# B2B_Connectors.net
KiCad netlist of a schematic drawn in Altium Designer
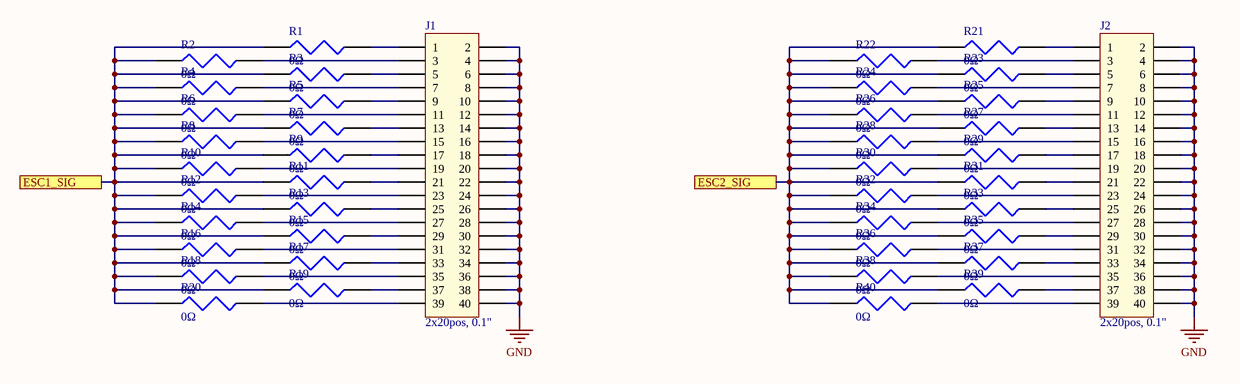
[diagram p0: B2B_Connectors.SchDoc]

(export (version "E")
  (design (tool "Eeschema 10.0.6"))
  (components
    (comp (ref "J1")
      (value "2x20pos, 0.1\"")
      (footprint "1979")
      (description "Adafruit STACKING HEADER RASPBERRY PI")
      (fields (field (name "MANUFACTURER") "Adafruit") (field (name "PART NUMBER") "1979"))
      (libsource (lib "MinesROV") (part "1979"))
    )
    (comp (ref "J2")
      (value "2x20pos, 0.1\"")
      (footprint "1979")
      (description "Adafruit STACKING HEADER RASPBERRY PI")
      (fields (field (name "MANUFACTURER") "Adafruit") (field (name "PART NUMBER") "1979"))
      (libsource (lib "MinesROV") (part "1979"))
    )
    (comp (ref "R1")
      (value "0Ω")
      (footprint "RMCF1206")
      (description "Stackpole RES 0 OHM 1/4W 1206")
      (fields
        (field (name "PART NUMBER") "RMCF1206ZT0R00")
        (field (name "MANUFACTURER") "Stackpole Electronics Inc")
      )
      (libsource (lib "MinesROV") (part "RMCF1206ZT0R00"))
    )
    (comp (ref "R2")
      (value "0Ω")
      (footprint "RMCF1206")
      (description "Stackpole RES 0 OHM 1/4W 1206")
      (fields
        (field (name "PART NUMBER") "RMCF1206ZT0R00")
        (field (name "MANUFACTURER") "Stackpole Electronics Inc")
      )
      (libsource (lib "MinesROV") (part "RMCF1206ZT0R00"))
    )
    (comp (ref "R3")
      (value "0Ω")
      (footprint "RMCF1206")
      (description "Stackpole RES 0 OHM 1/4W 1206")
      (fields
        (field (name "PART NUMBER") "RMCF1206ZT0R00")
        (field (name "MANUFACTURER") "Stackpole Electronics Inc")
      )
      (libsource (lib "MinesROV") (part "RMCF1206ZT0R00"))
    )
    (comp (ref "R4")
      (value "0Ω")
      (footprint "RMCF1206")
      (description "Stackpole RES 0 OHM 1/4W 1206")
      (fields
        (field (name "PART NUMBER") "RMCF1206ZT0R00")
        (field (name "MANUFACTURER") "Stackpole Electronics Inc")
      )
      (libsource (lib "MinesROV") (part "RMCF1206ZT0R00"))
    )
    (comp (ref "R5")
      (value "0Ω")
      (footprint "RMCF1206")
      (description "Stackpole RES 0 OHM 1/4W 1206")
      (fields
        (field (name "PART NUMBER") "RMCF1206ZT0R00")
        (field (name "MANUFACTURER") "Stackpole Electronics Inc")
      )
      (libsource (lib "MinesROV") (part "RMCF1206ZT0R00"))
    )
    (comp (ref "R6")
      (value "0Ω")
      (footprint "RMCF1206")
      (description "Stackpole RES 0 OHM 1/4W 1206")
      (fields
        (field (name "PART NUMBER") "RMCF1206ZT0R00")
        (field (name "MANUFACTURER") "Stackpole Electronics Inc")
      )
      (libsource (lib "MinesROV") (part "RMCF1206ZT0R00"))
    )
    (comp (ref "R7")
      (value "0Ω")
      (footprint "RMCF1206")
      (description "Stackpole RES 0 OHM 1/4W 1206")
      (fields
        (field (name "PART NUMBER") "RMCF1206ZT0R00")
        (field (name "MANUFACTURER") "Stackpole Electronics Inc")
      )
      (libsource (lib "MinesROV") (part "RMCF1206ZT0R00"))
    )
    (comp (ref "R8")
      (value "0Ω")
      (footprint "RMCF1206")
      (description "Stackpole RES 0 OHM 1/4W 1206")
      (fields
        (field (name "PART NUMBER") "RMCF1206ZT0R00")
        (field (name "MANUFACTURER") "Stackpole Electronics Inc")
      )
      (libsource (lib "MinesROV") (part "RMCF1206ZT0R00"))
    )
    (comp (ref "R9")
      (value "0Ω")
      (footprint "RMCF1206")
      (description "Stackpole RES 0 OHM 1/4W 1206")
      (fields
        (field (name "PART NUMBER") "RMCF1206ZT0R00")
        (field (name "MANUFACTURER") "Stackpole Electronics Inc")
      )
      (libsource (lib "MinesROV") (part "RMCF1206ZT0R00"))
    )
    (comp (ref "R10")
      (value "0Ω")
      (footprint "RMCF1206")
      (description "Stackpole RES 0 OHM 1/4W 1206")
      (fields
        (field (name "PART NUMBER") "RMCF1206ZT0R00")
        (field (name "MANUFACTURER") "Stackpole Electronics Inc")
      )
      (libsource (lib "MinesROV") (part "RMCF1206ZT0R00"))
    )
    (comp (ref "R11")
      (value "0Ω")
      (footprint "RMCF1206")
      (description "Stackpole RES 0 OHM 1/4W 1206")
      (fields
        (field (name "PART NUMBER") "RMCF1206ZT0R00")
        (field (name "MANUFACTURER") "Stackpole Electronics Inc")
      )
      (libsource (lib "MinesROV") (part "RMCF1206ZT0R00"))
    )
    (comp (ref "R12")
      (value "0Ω")
      (footprint "RMCF1206")
      (description "Stackpole RES 0 OHM 1/4W 1206")
      (fields
        (field (name "PART NUMBER") "RMCF1206ZT0R00")
        (field (name "MANUFACTURER") "Stackpole Electronics Inc")
      )
      (libsource (lib "MinesROV") (part "RMCF1206ZT0R00"))
    )
    (comp (ref "R13")
      (value "0Ω")
      (footprint "RMCF1206")
      (description "Stackpole RES 0 OHM 1/4W 1206")
      (fields
        (field (name "PART NUMBER") "RMCF1206ZT0R00")
        (field (name "MANUFACTURER") "Stackpole Electronics Inc")
      )
      (libsource (lib "MinesROV") (part "RMCF1206ZT0R00"))
    )
    (comp (ref "R14")
      (value "0Ω")
      (footprint "RMCF1206")
      (description "Stackpole RES 0 OHM 1/4W 1206")
      (fields
        (field (name "PART NUMBER") "RMCF1206ZT0R00")
        (field (name "MANUFACTURER") "Stackpole Electronics Inc")
      )
      (libsource (lib "MinesROV") (part "RMCF1206ZT0R00"))
    )
    (comp (ref "R15")
      (value "0Ω")
      (footprint "RMCF1206")
      (description "Stackpole RES 0 OHM 1/4W 1206")
      (fields
        (field (name "PART NUMBER") "RMCF1206ZT0R00")
        (field (name "MANUFACTURER") "Stackpole Electronics Inc")
      )
      (libsource (lib "MinesROV") (part "RMCF1206ZT0R00"))
    )
    (comp (ref "R16")
      (value "0Ω")
      (footprint "RMCF1206")
      (description "Stackpole RES 0 OHM 1/4W 1206")
      (fields
        (field (name "PART NUMBER") "RMCF1206ZT0R00")
        (field (name "MANUFACTURER") "Stackpole Electronics Inc")
      )
      (libsource (lib "MinesROV") (part "RMCF1206ZT0R00"))
    )
    (comp (ref "R17")
      (value "0Ω")
      (footprint "RMCF1206")
      (description "Stackpole RES 0 OHM 1/4W 1206")
      (fields
        (field (name "PART NUMBER") "RMCF1206ZT0R00")
        (field (name "MANUFACTURER") "Stackpole Electronics Inc")
      )
      (libsource (lib "MinesROV") (part "RMCF1206ZT0R00"))
    )
    (comp (ref "R18")
      (value "0Ω")
      (footprint "RMCF1206")
      (description "Stackpole RES 0 OHM 1/4W 1206")
      (fields
        (field (name "PART NUMBER") "RMCF1206ZT0R00")
        (field (name "MANUFACTURER") "Stackpole Electronics Inc")
      )
      (libsource (lib "MinesROV") (part "RMCF1206ZT0R00"))
    )
    (comp (ref "R19")
      (value "0Ω")
      (footprint "RMCF1206")
      (description "Stackpole RES 0 OHM 1/4W 1206")
      (fields
        (field (name "PART NUMBER") "RMCF1206ZT0R00")
        (field (name "MANUFACTURER") "Stackpole Electronics Inc")
      )
      (libsource (lib "MinesROV") (part "RMCF1206ZT0R00"))
    )
    (comp (ref "R20")
      (value "0Ω")
      (footprint "RMCF1206")
      (description "Stackpole RES 0 OHM 1/4W 1206")
      (fields
        (field (name "PART NUMBER") "RMCF1206ZT0R00")
        (field (name "MANUFACTURER") "Stackpole Electronics Inc")
      )
      (libsource (lib "MinesROV") (part "RMCF1206ZT0R00"))
    )
    (comp (ref "R21")
      (value "0Ω")
      (footprint "RMCF1206")
      (description "Stackpole RES 0 OHM 1/4W 1206")
      (fields
        (field (name "PART NUMBER") "RMCF1206ZT0R00")
        (field (name "MANUFACTURER") "Stackpole Electronics Inc")
      )
      (libsource (lib "MinesROV") (part "RMCF1206ZT0R00"))
    )
    (comp (ref "R22")
      (value "0Ω")
      (footprint "RMCF1206")
      (description "Stackpole RES 0 OHM 1/4W 1206")
      (fields
        (field (name "PART NUMBER") "RMCF1206ZT0R00")
        (field (name "MANUFACTURER") "Stackpole Electronics Inc")
      )
      (libsource (lib "MinesROV") (part "RMCF1206ZT0R00"))
    )
    (comp (ref "R23")
      (value "0Ω")
      (footprint "RMCF1206")
      (description "Stackpole RES 0 OHM 1/4W 1206")
      (fields
        (field (name "PART NUMBER") "RMCF1206ZT0R00")
        (field (name "MANUFACTURER") "Stackpole Electronics Inc")
      )
      (libsource (lib "MinesROV") (part "RMCF1206ZT0R00"))
    )
    (comp (ref "R24")
      (value "0Ω")
      (footprint "RMCF1206")
      (description "Stackpole RES 0 OHM 1/4W 1206")
      (fields
        (field (name "PART NUMBER") "RMCF1206ZT0R00")
        (field (name "MANUFACTURER") "Stackpole Electronics Inc")
      )
      (libsource (lib "MinesROV") (part "RMCF1206ZT0R00"))
    )
    (comp (ref "R25")
      (value "0Ω")
      (footprint "RMCF1206")
      (description "Stackpole RES 0 OHM 1/4W 1206")
      (fields
        (field (name "PART NUMBER") "RMCF1206ZT0R00")
        (field (name "MANUFACTURER") "Stackpole Electronics Inc")
      )
      (libsource (lib "MinesROV") (part "RMCF1206ZT0R00"))
    )
    (comp (ref "R26")
      (value "0Ω")
      (footprint "RMCF1206")
      (description "Stackpole RES 0 OHM 1/4W 1206")
      (fields
        (field (name "PART NUMBER") "RMCF1206ZT0R00")
        (field (name "MANUFACTURER") "Stackpole Electronics Inc")
      )
      (libsource (lib "MinesROV") (part "RMCF1206ZT0R00"))
    )
    (comp (ref "R27")
      (value "0Ω")
      (footprint "RMCF1206")
      (description "Stackpole RES 0 OHM 1/4W 1206")
      (fields
        (field (name "PART NUMBER") "RMCF1206ZT0R00")
        (field (name "MANUFACTURER") "Stackpole Electronics Inc")
      )
      (libsource (lib "MinesROV") (part "RMCF1206ZT0R00"))
    )
    (comp (ref "R28")
      (value "0Ω")
      (footprint "RMCF1206")
      (description "Stackpole RES 0 OHM 1/4W 1206")
      (fields
        (field (name "PART NUMBER") "RMCF1206ZT0R00")
        (field (name "MANUFACTURER") "Stackpole Electronics Inc")
      )
      (libsource (lib "MinesROV") (part "RMCF1206ZT0R00"))
    )
    (comp (ref "R29")
      (value "0Ω")
      (footprint "RMCF1206")
      (description "Stackpole RES 0 OHM 1/4W 1206")
      (fields
        (field (name "PART NUMBER") "RMCF1206ZT0R00")
        (field (name "MANUFACTURER") "Stackpole Electronics Inc")
      )
      (libsource (lib "MinesROV") (part "RMCF1206ZT0R00"))
    )
    (comp (ref "R30")
      (value "0Ω")
      (footprint "RMCF1206")
      (description "Stackpole RES 0 OHM 1/4W 1206")
      (fields
        (field (name "PART NUMBER") "RMCF1206ZT0R00")
        (field (name "MANUFACTURER") "Stackpole Electronics Inc")
      )
      (libsource (lib "MinesROV") (part "RMCF1206ZT0R00"))
    )
    (comp (ref "R31")
      (value "0Ω")
      (footprint "RMCF1206")
      (description "Stackpole RES 0 OHM 1/4W 1206")
      (fields
        (field (name "PART NUMBER") "RMCF1206ZT0R00")
        (field (name "MANUFACTURER") "Stackpole Electronics Inc")
      )
      (libsource (lib "MinesROV") (part "RMCF1206ZT0R00"))
    )
    (comp (ref "R32")
      (value "0Ω")
      (footprint "RMCF1206")
      (description "Stackpole RES 0 OHM 1/4W 1206")
      (fields
        (field (name "PART NUMBER") "RMCF1206ZT0R00")
        (field (name "MANUFACTURER") "Stackpole Electronics Inc")
      )
      (libsource (lib "MinesROV") (part "RMCF1206ZT0R00"))
    )
    (comp (ref "R33")
      (value "0Ω")
      (footprint "RMCF1206")
      (description "Stackpole RES 0 OHM 1/4W 1206")
      (fields
        (field (name "PART NUMBER") "RMCF1206ZT0R00")
        (field (name "MANUFACTURER") "Stackpole Electronics Inc")
      )
      (libsource (lib "MinesROV") (part "RMCF1206ZT0R00"))
    )
    (comp (ref "R34")
      (value "0Ω")
      (footprint "RMCF1206")
      (description "Stackpole RES 0 OHM 1/4W 1206")
      (fields
        (field (name "PART NUMBER") "RMCF1206ZT0R00")
        (field (name "MANUFACTURER") "Stackpole Electronics Inc")
      )
      (libsource (lib "MinesROV") (part "RMCF1206ZT0R00"))
    )
    (comp (ref "R35")
      (value "0Ω")
      (footprint "RMCF1206")
      (description "Stackpole RES 0 OHM 1/4W 1206")
      (fields
        (field (name "PART NUMBER") "RMCF1206ZT0R00")
        (field (name "MANUFACTURER") "Stackpole Electronics Inc")
      )
      (libsource (lib "MinesROV") (part "RMCF1206ZT0R00"))
    )
    (comp (ref "R36")
      (value "0Ω")
      (footprint "RMCF1206")
      (description "Stackpole RES 0 OHM 1/4W 1206")
      (fields
        (field (name "PART NUMBER") "RMCF1206ZT0R00")
        (field (name "MANUFACTURER") "Stackpole Electronics Inc")
      )
      (libsource (lib "MinesROV") (part "RMCF1206ZT0R00"))
    )
    (comp (ref "R37")
      (value "0Ω")
      (footprint "RMCF1206")
      (description "Stackpole RES 0 OHM 1/4W 1206")
      (fields
        (field (name "PART NUMBER") "RMCF1206ZT0R00")
        (field (name "MANUFACTURER") "Stackpole Electronics Inc")
      )
      (libsource (lib "MinesROV") (part "RMCF1206ZT0R00"))
    )
    (comp (ref "R38")
      (value "0Ω")
      (footprint "RMCF1206")
      (description "Stackpole RES 0 OHM 1/4W 1206")
      (fields
        (field (name "PART NUMBER") "RMCF1206ZT0R00")
        (field (name "MANUFACTURER") "Stackpole Electronics Inc")
      )
      (libsource (lib "MinesROV") (part "RMCF1206ZT0R00"))
    )
    (comp (ref "R39")
      (value "0Ω")
      (footprint "RMCF1206")
      (description "Stackpole RES 0 OHM 1/4W 1206")
      (fields
        (field (name "PART NUMBER") "RMCF1206ZT0R00")
        (field (name "MANUFACTURER") "Stackpole Electronics Inc")
      )
      (libsource (lib "MinesROV") (part "RMCF1206ZT0R00"))
    )
    (comp (ref "R40")
      (value "0Ω")
      (footprint "RMCF1206")
      (description "Stackpole RES 0 OHM 1/4W 1206")
      (fields
        (field (name "PART NUMBER") "RMCF1206ZT0R00")
        (field (name "MANUFACTURER") "Stackpole Electronics Inc")
      )
      (libsource (lib "MinesROV") (part "RMCF1206ZT0R00"))
    )
  )
  (nets
    (net (code "1") (name "/ESC1_SIG") (class "Default")
      (node (ref "R1") (pin "1") (pinfunction "1_1") (pintype "passive"))
      (node (ref "R10") (pin "1") (pinfunction "1_1") (pintype "passive"))
      (node (ref "R11") (pin "1") (pinfunction "1_1") (pintype "passive"))
      (node (ref "R12") (pin "1") (pinfunction "1_1") (pintype "passive"))
      (node (ref "R13") (pin "1") (pinfunction "1_1") (pintype "passive"))
      (node (ref "R14") (pin "1") (pinfunction "1_1") (pintype "passive"))
      (node (ref "R15") (pin "1") (pinfunction "1_1") (pintype "passive"))
      (node (ref "R16") (pin "1") (pinfunction "1_1") (pintype "passive"))
      (node (ref "R17") (pin "1") (pinfunction "1_1") (pintype "passive"))
      (node (ref "R18") (pin "1") (pinfunction "1_1") (pintype "passive"))
      (node (ref "R19") (pin "1") (pinfunction "1_1") (pintype "passive"))
      (node (ref "R2") (pin "1") (pinfunction "1_1") (pintype "passive"))
      (node (ref "R20") (pin "1") (pinfunction "1_1") (pintype "passive"))
      (node (ref "R3") (pin "1") (pinfunction "1_1") (pintype "passive"))
      (node (ref "R4") (pin "1") (pinfunction "1_1") (pintype "passive"))
      (node (ref "R5") (pin "1") (pinfunction "1_1") (pintype "passive"))
      (node (ref "R6") (pin "1") (pinfunction "1_1") (pintype "passive"))
      (node (ref "R7") (pin "1") (pinfunction "1_1") (pintype "passive"))
      (node (ref "R8") (pin "1") (pinfunction "1_1") (pintype "passive"))
      (node (ref "R9") (pin "1") (pinfunction "1_1") (pintype "passive"))
    )
    (net (code "2") (name "/ESC2_SIG") (class "Default")
      (node (ref "R21") (pin "1") (pinfunction "1_1") (pintype "passive"))
      (node (ref "R22") (pin "1") (pinfunction "1_1") (pintype "passive"))
      (node (ref "R23") (pin "1") (pinfunction "1_1") (pintype "passive"))
      (node (ref "R24") (pin "1") (pinfunction "1_1") (pintype "passive"))
      (node (ref "R25") (pin "1") (pinfunction "1_1") (pintype "passive"))
      (node (ref "R26") (pin "1") (pinfunction "1_1") (pintype "passive"))
      (node (ref "R27") (pin "1") (pinfunction "1_1") (pintype "passive"))
      (node (ref "R28") (pin "1") (pinfunction "1_1") (pintype "passive"))
      (node (ref "R29") (pin "1") (pinfunction "1_1") (pintype "passive"))
      (node (ref "R30") (pin "1") (pinfunction "1_1") (pintype "passive"))
      (node (ref "R31") (pin "1") (pinfunction "1_1") (pintype "passive"))
      (node (ref "R32") (pin "1") (pinfunction "1_1") (pintype "passive"))
      (node (ref "R33") (pin "1") (pinfunction "1_1") (pintype "passive"))
      (node (ref "R34") (pin "1") (pinfunction "1_1") (pintype "passive"))
      (node (ref "R35") (pin "1") (pinfunction "1_1") (pintype "passive"))
      (node (ref "R36") (pin "1") (pinfunction "1_1") (pintype "passive"))
      (node (ref "R37") (pin "1") (pinfunction "1_1") (pintype "passive"))
      (node (ref "R38") (pin "1") (pinfunction "1_1") (pintype "passive"))
      (node (ref "R39") (pin "1") (pinfunction "1_1") (pintype "passive"))
      (node (ref "R40") (pin "1") (pinfunction "1_1") (pintype "passive"))
    )
    (net (code "3") (name "GND") (class "Default")
      (node (ref "J1") (pin "10") (pinfunction "10_10") (pintype "passive"))
      (node (ref "J1") (pin "12") (pinfunction "12_12") (pintype "passive"))
      (node (ref "J1") (pin "14") (pinfunction "14_14") (pintype "passive"))
      (node (ref "J1") (pin "16") (pinfunction "16_16") (pintype "passive"))
      (node (ref "J1") (pin "18") (pinfunction "18_18") (pintype "passive"))
      (node (ref "J1") (pin "2") (pinfunction "2_2") (pintype "passive"))
      (node (ref "J1") (pin "20") (pinfunction "20_20") (pintype "passive"))
      (node (ref "J1") (pin "22") (pinfunction "22_22") (pintype "passive"))
      (node (ref "J1") (pin "24") (pinfunction "24_24") (pintype "passive"))
      (node (ref "J1") (pin "26") (pinfunction "26_26") (pintype "passive"))
      (node (ref "J1") (pin "28") (pinfunction "28_28") (pintype "passive"))
      (node (ref "J1") (pin "30") (pinfunction "30_30") (pintype "passive"))
      (node (ref "J1") (pin "32") (pinfunction "32_32") (pintype "passive"))
      (node (ref "J1") (pin "34") (pinfunction "34_34") (pintype "passive"))
      (node (ref "J1") (pin "36") (pinfunction "36_36") (pintype "passive"))
      (node (ref "J1") (pin "38") (pinfunction "38_38") (pintype "passive"))
      (node (ref "J1") (pin "4") (pinfunction "4_4") (pintype "passive"))
      (node (ref "J1") (pin "40") (pinfunction "40_40") (pintype "passive"))
      (node (ref "J1") (pin "6") (pinfunction "6_6") (pintype "passive"))
      (node (ref "J1") (pin "8") (pinfunction "8_8") (pintype "passive"))
      (node (ref "J2") (pin "10") (pinfunction "10_10") (pintype "passive"))
      (node (ref "J2") (pin "12") (pinfunction "12_12") (pintype "passive"))
      (node (ref "J2") (pin "14") (pinfunction "14_14") (pintype "passive"))
      (node (ref "J2") (pin "16") (pinfunction "16_16") (pintype "passive"))
      (node (ref "J2") (pin "18") (pinfunction "18_18") (pintype "passive"))
      (node (ref "J2") (pin "2") (pinfunction "2_2") (pintype "passive"))
      (node (ref "J2") (pin "20") (pinfunction "20_20") (pintype "passive"))
      (node (ref "J2") (pin "22") (pinfunction "22_22") (pintype "passive"))
      (node (ref "J2") (pin "24") (pinfunction "24_24") (pintype "passive"))
      (node (ref "J2") (pin "26") (pinfunction "26_26") (pintype "passive"))
      (node (ref "J2") (pin "28") (pinfunction "28_28") (pintype "passive"))
      (node (ref "J2") (pin "30") (pinfunction "30_30") (pintype "passive"))
      (node (ref "J2") (pin "32") (pinfunction "32_32") (pintype "passive"))
      (node (ref "J2") (pin "34") (pinfunction "34_34") (pintype "passive"))
      (node (ref "J2") (pin "36") (pinfunction "36_36") (pintype "passive"))
      (node (ref "J2") (pin "38") (pinfunction "38_38") (pintype "passive"))
      (node (ref "J2") (pin "4") (pinfunction "4_4") (pintype "passive"))
      (node (ref "J2") (pin "40") (pinfunction "40_40") (pintype "passive"))
      (node (ref "J2") (pin "6") (pinfunction "6_6") (pintype "passive"))
      (node (ref "J2") (pin "8") (pinfunction "8_8") (pintype "passive"))
    )
    (net (code "4") (name "Net-(J1-Pad1)") (class "Default")
      (node (ref "J1") (pin "1") (pinfunction "1_1") (pintype "passive"))
      (node (ref "R1") (pin "2") (pinfunction "2_2") (pintype "passive"))
    )
    (net (code "5") (name "Net-(J1-Pad3)") (class "Default")
      (node (ref "J1") (pin "3") (pinfunction "3_3") (pintype "passive"))
      (node (ref "R2") (pin "2") (pinfunction "2_2") (pintype "passive"))
    )
    (net (code "6") (name "Net-(J1-Pad5)") (class "Default")
      (node (ref "J1") (pin "5") (pinfunction "5_5") (pintype "passive"))
      (node (ref "R3") (pin "2") (pinfunction "2_2") (pintype "passive"))
    )
    (net (code "7") (name "Net-(J1-Pad7)") (class "Default")
      (node (ref "J1") (pin "7") (pinfunction "7_7") (pintype "passive"))
      (node (ref "R4") (pin "2") (pinfunction "2_2") (pintype "passive"))
    )
    (net (code "8") (name "Net-(J1-Pad9)") (class "Default")
      (node (ref "J1") (pin "9") (pinfunction "9_9") (pintype "passive"))
      (node (ref "R5") (pin "2") (pinfunction "2_2") (pintype "passive"))
    )
    (net (code "9") (name "Net-(J1-Pad11)") (class "Default")
      (node (ref "J1") (pin "11") (pinfunction "11_11") (pintype "passive"))
      (node (ref "R6") (pin "2") (pinfunction "2_2") (pintype "passive"))
    )
    (net (code "10") (name "Net-(J1-Pad13)") (class "Default")
      (node (ref "J1") (pin "13") (pinfunction "13_13") (pintype "passive"))
      (node (ref "R7") (pin "2") (pinfunction "2_2") (pintype "passive"))
    )
    (net (code "11") (name "Net-(J1-Pad15)") (class "Default")
      (node (ref "J1") (pin "15") (pinfunction "15_15") (pintype "passive"))
      (node (ref "R8") (pin "2") (pinfunction "2_2") (pintype "passive"))
    )
    (net (code "12") (name "Net-(J1-Pad17)") (class "Default")
      (node (ref "J1") (pin "17") (pinfunction "17_17") (pintype "passive"))
      (node (ref "R9") (pin "2") (pinfunction "2_2") (pintype "passive"))
    )
    (net (code "13") (name "Net-(J1-Pad19)") (class "Default")
      (node (ref "J1") (pin "19") (pinfunction "19_19") (pintype "passive"))
      (node (ref "R10") (pin "2") (pinfunction "2_2") (pintype "passive"))
    )
    (net (code "14") (name "Net-(J1-Pad21)") (class "Default")
      (node (ref "J1") (pin "21") (pinfunction "21_21") (pintype "passive"))
      (node (ref "R11") (pin "2") (pinfunction "2_2") (pintype "passive"))
    )
    (net (code "15") (name "Net-(J1-Pad23)") (class "Default")
      (node (ref "J1") (pin "23") (pinfunction "23_23") (pintype "passive"))
      (node (ref "R12") (pin "2") (pinfunction "2_2") (pintype "passive"))
    )
    (net (code "16") (name "Net-(J1-Pad25)") (class "Default")
      (node (ref "J1") (pin "25") (pinfunction "25_25") (pintype "passive"))
      (node (ref "R13") (pin "2") (pinfunction "2_2") (pintype "passive"))
    )
    (net (code "17") (name "Net-(J1-Pad27)") (class "Default")
      (node (ref "J1") (pin "27") (pinfunction "27_27") (pintype "passive"))
      (node (ref "R14") (pin "2") (pinfunction "2_2") (pintype "passive"))
    )
    (net (code "18") (name "Net-(J1-Pad29)") (class "Default")
      (node (ref "J1") (pin "29") (pinfunction "29_29") (pintype "passive"))
      (node (ref "R15") (pin "2") (pinfunction "2_2") (pintype "passive"))
    )
    (net (code "19") (name "Net-(J1-Pad31)") (class "Default")
      (node (ref "J1") (pin "31") (pinfunction "31_31") (pintype "passive"))
      (node (ref "R16") (pin "2") (pinfunction "2_2") (pintype "passive"))
    )
    (net (code "20") (name "Net-(J1-Pad33)") (class "Default")
      (node (ref "J1") (pin "33") (pinfunction "33_33") (pintype "passive"))
      (node (ref "R17") (pin "2") (pinfunction "2_2") (pintype "passive"))
    )
    (net (code "21") (name "Net-(J1-Pad35)") (class "Default")
      (node (ref "J1") (pin "35") (pinfunction "35_35") (pintype "passive"))
      (node (ref "R18") (pin "2") (pinfunction "2_2") (pintype "passive"))
    )
    (net (code "22") (name "Net-(J1-Pad37)") (class "Default")
      (node (ref "J1") (pin "37") (pinfunction "37_37") (pintype "passive"))
      (node (ref "R19") (pin "2") (pinfunction "2_2") (pintype "passive"))
    )
    (net (code "23") (name "Net-(J1-Pad39)") (class "Default")
      (node (ref "J1") (pin "39") (pinfunction "39_39") (pintype "passive"))
      (node (ref "R20") (pin "2") (pinfunction "2_2") (pintype "passive"))
    )
    (net (code "24") (name "Net-(J2-Pad1)") (class "Default")
      (node (ref "J2") (pin "1") (pinfunction "1_1") (pintype "passive"))
      (node (ref "R21") (pin "2") (pinfunction "2_2") (pintype "passive"))
    )
    (net (code "25") (name "Net-(J2-Pad3)") (class "Default")
      (node (ref "J2") (pin "3") (pinfunction "3_3") (pintype "passive"))
      (node (ref "R22") (pin "2") (pinfunction "2_2") (pintype "passive"))
    )
    (net (code "26") (name "Net-(J2-Pad5)") (class "Default")
      (node (ref "J2") (pin "5") (pinfunction "5_5") (pintype "passive"))
      (node (ref "R23") (pin "2") (pinfunction "2_2") (pintype "passive"))
    )
    (net (code "27") (name "Net-(J2-Pad7)") (class "Default")
      (node (ref "J2") (pin "7") (pinfunction "7_7") (pintype "passive"))
      (node (ref "R24") (pin "2") (pinfunction "2_2") (pintype "passive"))
    )
    (net (code "28") (name "Net-(J2-Pad9)") (class "Default")
      (node (ref "J2") (pin "9") (pinfunction "9_9") (pintype "passive"))
      (node (ref "R25") (pin "2") (pinfunction "2_2") (pintype "passive"))
    )
    (net (code "29") (name "Net-(J2-Pad11)") (class "Default")
      (node (ref "J2") (pin "11") (pinfunction "11_11") (pintype "passive"))
      (node (ref "R26") (pin "2") (pinfunction "2_2") (pintype "passive"))
    )
    (net (code "30") (name "Net-(J2-Pad13)") (class "Default")
      (node (ref "J2") (pin "13") (pinfunction "13_13") (pintype "passive"))
      (node (ref "R27") (pin "2") (pinfunction "2_2") (pintype "passive"))
    )
    (net (code "31") (name "Net-(J2-Pad15)") (class "Default")
      (node (ref "J2") (pin "15") (pinfunction "15_15") (pintype "passive"))
      (node (ref "R28") (pin "2") (pinfunction "2_2") (pintype "passive"))
    )
    (net (code "32") (name "Net-(J2-Pad17)") (class "Default")
      (node (ref "J2") (pin "17") (pinfunction "17_17") (pintype "passive"))
      (node (ref "R29") (pin "2") (pinfunction "2_2") (pintype "passive"))
    )
    (net (code "33") (name "Net-(J2-Pad19)") (class "Default")
      (node (ref "J2") (pin "19") (pinfunction "19_19") (pintype "passive"))
      (node (ref "R30") (pin "2") (pinfunction "2_2") (pintype "passive"))
    )
    (net (code "34") (name "Net-(J2-Pad21)") (class "Default")
      (node (ref "J2") (pin "21") (pinfunction "21_21") (pintype "passive"))
      (node (ref "R31") (pin "2") (pinfunction "2_2") (pintype "passive"))
    )
    (net (code "35") (name "Net-(J2-Pad23)") (class "Default")
      (node (ref "J2") (pin "23") (pinfunction "23_23") (pintype "passive"))
      (node (ref "R32") (pin "2") (pinfunction "2_2") (pintype "passive"))
    )
    (net (code "36") (name "Net-(J2-Pad25)") (class "Default")
      (node (ref "J2") (pin "25") (pinfunction "25_25") (pintype "passive"))
      (node (ref "R33") (pin "2") (pinfunction "2_2") (pintype "passive"))
    )
    (net (code "37") (name "Net-(J2-Pad27)") (class "Default")
      (node (ref "J2") (pin "27") (pinfunction "27_27") (pintype "passive"))
      (node (ref "R34") (pin "2") (pinfunction "2_2") (pintype "passive"))
    )
    (net (code "38") (name "Net-(J2-Pad29)") (class "Default")
      (node (ref "J2") (pin "29") (pinfunction "29_29") (pintype "passive"))
      (node (ref "R35") (pin "2") (pinfunction "2_2") (pintype "passive"))
    )
    (net (code "39") (name "Net-(J2-Pad31)") (class "Default")
      (node (ref "J2") (pin "31") (pinfunction "31_31") (pintype "passive"))
      (node (ref "R36") (pin "2") (pinfunction "2_2") (pintype "passive"))
    )
    (net (code "40") (name "Net-(J2-Pad33)") (class "Default")
      (node (ref "J2") (pin "33") (pinfunction "33_33") (pintype "passive"))
      (node (ref "R37") (pin "2") (pinfunction "2_2") (pintype "passive"))
    )
    (net (code "41") (name "Net-(J2-Pad35)") (class "Default")
      (node (ref "J2") (pin "35") (pinfunction "35_35") (pintype "passive"))
      (node (ref "R38") (pin "2") (pinfunction "2_2") (pintype "passive"))
    )
    (net (code "42") (name "Net-(J2-Pad37)") (class "Default")
      (node (ref "J2") (pin "37") (pinfunction "37_37") (pintype "passive"))
      (node (ref "R39") (pin "2") (pinfunction "2_2") (pintype "passive"))
    )
    (net (code "43") (name "Net-(J2-Pad39)") (class "Default")
      (node (ref "J2") (pin "39") (pinfunction "39_39") (pintype "passive"))
      (node (ref "R40") (pin "2") (pinfunction "2_2") (pintype "passive"))
    )
  )
)
